# pumpkin.net
KiCad netlist of a schematic drawn in EAGLE
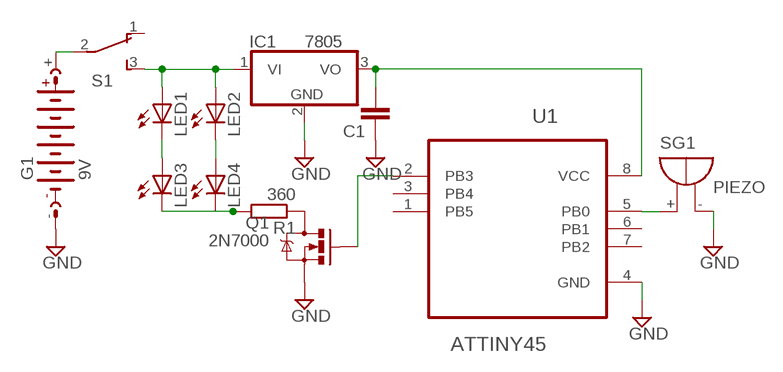
[diagram p0: schematic, sheet 1]

(export (version "E")
  (design (tool "Eeschema 10.0.6"))
  (components
    (comp (ref "C1")
      (value "C-EU025-024X044")
      (footprint "eagle-import:C025-024X044")
      (libsource (lib "eagle-import") (part "C-EU025-024X044"))
    )
    (comp (ref "G1")
      (value "9V")
      (footprint "eagle-import:AB9V")
      (libsource (lib "eagle-import") (part "AB9V"))
    )
    (comp (ref "IC1")
      (value "7805")
      (footprint "eagle-import:TO220V")
      (libsource (lib "eagle-import") (part "78TV05"))
    )
    (comp (ref "LED1")
      (value "LED5MM")
      (footprint "eagle-import:LED5MM")
      (libsource (lib "eagle-import") (part "LED5MM"))
    )
    (comp (ref "LED2")
      (value "LED5MM")
      (footprint "eagle-import:LED5MM")
      (libsource (lib "eagle-import") (part "LED5MM"))
    )
    (comp (ref "LED3")
      (value "LED5MM")
      (footprint "eagle-import:LED5MM")
      (libsource (lib "eagle-import") (part "LED5MM"))
    )
    (comp (ref "LED4")
      (value "LED5MM")
      (footprint "eagle-import:LED5MM")
      (libsource (lib "eagle-import") (part "LED5MM"))
    )
    (comp (ref "Q1")
      (value "2N7000")
      (footprint "eagle-import:TO92-")
      (libsource (lib "eagle-import") (part "MOSFET-NCHANNEL2N7000INLINE"))
    )
    (comp (ref "R1")
      (value "360")
      (footprint "eagle-import:0204_5")
      (libsource (lib "eagle-import") (part "R-EU_0204/5"))
    )
    (comp (ref "S1")
      (value "TL36PO")
      (footprint "eagle-import:TL3XPO")
      (libsource (lib "eagle-import") (part "TL36PO"))
    )
    (comp (ref "SG1")
      (value "PIEZO")
      (footprint "eagle-import:F_DB18")
      (libsource (lib "eagle-import") (part "F/DB18"))
    )
    (comp (ref "U1")
      (value "ATTINY45")
      (footprint "eagle-import:DIP254P762X533-8")
      (fields (field (name "MPN") "ATTINY45-20PU"))
      (libsource (lib "eagle-import") (part "ATTINY45-20PU"))
    )
  )
  (nets
    (net (code "1") (name "GND") (class "Default")
      (node (ref "C1") (pin "1") (pinfunction "1_1") (pintype "passive"))
      (node (ref "G1") (pin "-") (pinfunction "-_-") (pintype "passive"))
      (node (ref "IC1") (pin "2") (pinfunction "GND_2") (pintype "passive"))
      (node (ref "Q1") (pin "3") (pinfunction "S_3") (pintype "passive"))
      (node (ref "SG1") (pin "-") (pinfunction "-_-") (pintype "passive"))
      (node (ref "U1") (pin "4") (pinfunction "GND_4") (pintype "passive"))
    )
    (net (code "2") (name "Net-(IC1-VI)") (class "Default")
      (node (ref "IC1") (pin "1") (pinfunction "VI_1") (pintype "input"))
      (node (ref "LED1") (pin "A") (pinfunction "A_A") (pintype "passive"))
      (node (ref "LED2") (pin "A") (pinfunction "A_A") (pintype "passive"))
      (node (ref "S1") (pin "3") (pinfunction "S_3") (pintype "passive"))
    )
    (net (code "3") (name "Net-(IC1-VO)") (class "Default")
      (node (ref "C1") (pin "2") (pinfunction "2_2") (pintype "passive"))
      (node (ref "IC1") (pin "3") (pinfunction "VO_3") (pintype "passive"))
      (node (ref "U1") (pin "8") (pinfunction "VCC_8") (pintype "power_in"))
    )
    (net (code "4") (name "Net-(LED1-C)") (class "Default")
      (node (ref "LED1") (pin "K") (pinfunction "C_K") (pintype "passive"))
      (node (ref "LED3") (pin "A") (pinfunction "A_A") (pintype "passive"))
    )
    (net (code "5") (name "Net-(LED2-C)") (class "Default")
      (node (ref "LED2") (pin "K") (pinfunction "C_K") (pintype "passive"))
      (node (ref "LED4") (pin "A") (pinfunction "A_A") (pintype "passive"))
    )
    (net (code "6") (name "Net-(LED3-C)") (class "Default")
      (node (ref "LED3") (pin "K") (pinfunction "C_K") (pintype "passive"))
      (node (ref "LED4") (pin "K") (pinfunction "C_K") (pintype "passive"))
      (node (ref "R1") (pin "2") (pinfunction "2_2") (pintype "passive"))
    )
    (net (code "7") (name "Net-(Q1-D)") (class "Default")
      (node (ref "Q1") (pin "1") (pinfunction "D_1") (pintype "passive"))
      (node (ref "R1") (pin "1") (pinfunction "1_1") (pintype "passive"))
    )
    (net (code "8") (name "Net-(Q1-G)") (class "Default")
      (node (ref "Q1") (pin "2") (pinfunction "G_2") (pintype "passive"))
      (node (ref "U1") (pin "2") (pinfunction "PB3_2") (pintype "bidirectional"))
    )
    (net (code "9") (name "Net-(S1-P)") (class "Default")
      (node (ref "G1") (pin "+") (pinfunction "+_+") (pintype "passive"))
      (node (ref "S1") (pin "2") (pinfunction "P_2") (pintype "passive"))
    )
    (net (code "10") (name "Net-(U1-PB0)") (class "Default")
      (node (ref "SG1") (pin "+") (pinfunction "+_+") (pintype "passive"))
      (node (ref "U1") (pin "5") (pinfunction "PB0_5") (pintype "bidirectional"))
    )
    (net (code "11") (name "unconnected-(S1-O-Pad1)") (class "Default")
      (node (ref "S1") (pin "1") (pinfunction "O_1") (pintype "passive"))
    )
    (net (code "12") (name "unconnected-(U1-PB1-Pad6)") (class "Default")
      (node (ref "U1") (pin "6") (pinfunction "PB1_6") (pintype "bidirectional"))
    )
    (net (code "13") (name "unconnected-(U1-PB2-Pad7)") (class "Default")
      (node (ref "U1") (pin "7") (pinfunction "PB2_7") (pintype "bidirectional"))
    )
    (net (code "14") (name "unconnected-(U1-PB4-Pad3)") (class "Default")
      (node (ref "U1") (pin "3") (pinfunction "PB4_3") (pintype "bidirectional"))
    )
    (net (code "15") (name "unconnected-(U1-PB5-Pad1)") (class "Default")
      (node (ref "U1") (pin "1") (pinfunction "PB5_1") (pintype "bidirectional"))
    )
  )
)
